# Schematic.net
KiCad netlist of a schematic drawn in EAGLE
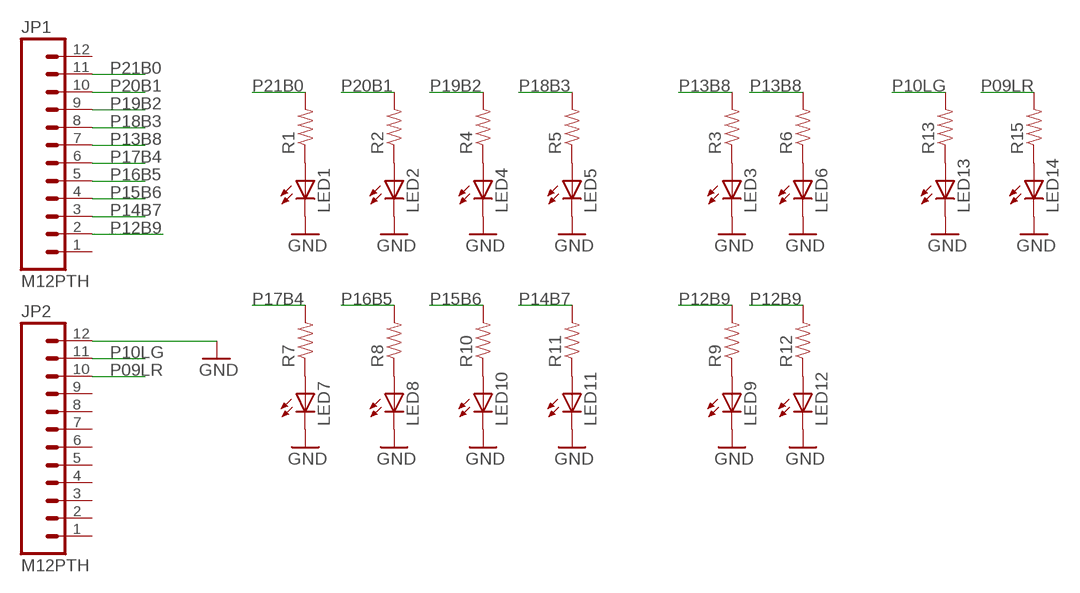
[diagram p0: schematic, sheet 1]

(export (version "E")
  (design (tool "Eeschema 10.0.6"))
  (components
    (comp (ref "JP1")
      (value "M12PTH")
      (footprint "eagle-import:1X12")
      (libsource (lib "eagle-import") (part "M12PTH"))
    )
    (comp (ref "JP2")
      (value "M12PTH")
      (footprint "eagle-import:1X12")
      (libsource (lib "eagle-import") (part "M12PTH"))
    )
    (comp (ref "LED1")
      (value "LEDCHIPLED_0805")
      (footprint "eagle-import:CHIPLED_0805")
      (libsource (lib "eagle-import") (part "LEDCHIPLED_0805"))
    )
    (comp (ref "LED2")
      (value "LEDCHIPLED_0805")
      (footprint "eagle-import:CHIPLED_0805")
      (libsource (lib "eagle-import") (part "LEDCHIPLED_0805"))
    )
    (comp (ref "LED3")
      (value "LEDCHIPLED_0805")
      (footprint "eagle-import:CHIPLED_0805")
      (libsource (lib "eagle-import") (part "LEDCHIPLED_0805"))
    )
    (comp (ref "LED4")
      (value "LEDCHIPLED_0805")
      (footprint "eagle-import:CHIPLED_0805")
      (libsource (lib "eagle-import") (part "LEDCHIPLED_0805"))
    )
    (comp (ref "LED5")
      (value "LEDCHIPLED_0805")
      (footprint "eagle-import:CHIPLED_0805")
      (libsource (lib "eagle-import") (part "LEDCHIPLED_0805"))
    )
    (comp (ref "LED6")
      (value "LEDCHIPLED_0805")
      (footprint "eagle-import:CHIPLED_0805")
      (libsource (lib "eagle-import") (part "LEDCHIPLED_0805"))
    )
    (comp (ref "LED7")
      (value "LEDCHIPLED_0805")
      (footprint "eagle-import:CHIPLED_0805")
      (libsource (lib "eagle-import") (part "LEDCHIPLED_0805"))
    )
    (comp (ref "LED8")
      (value "LEDCHIPLED_0805")
      (footprint "eagle-import:CHIPLED_0805")
      (libsource (lib "eagle-import") (part "LEDCHIPLED_0805"))
    )
    (comp (ref "LED9")
      (value "LEDCHIPLED_0805")
      (footprint "eagle-import:CHIPLED_0805")
      (libsource (lib "eagle-import") (part "LEDCHIPLED_0805"))
    )
    (comp (ref "LED10")
      (value "LEDCHIPLED_0805")
      (footprint "eagle-import:CHIPLED_0805")
      (libsource (lib "eagle-import") (part "LEDCHIPLED_0805"))
    )
    (comp (ref "LED11")
      (value "LEDCHIPLED_0805")
      (footprint "eagle-import:CHIPLED_0805")
      (libsource (lib "eagle-import") (part "LEDCHIPLED_0805"))
    )
    (comp (ref "LED12")
      (value "LEDCHIPLED_0805")
      (footprint "eagle-import:CHIPLED_0805")
      (libsource (lib "eagle-import") (part "LEDCHIPLED_0805"))
    )
    (comp (ref "LED13")
      (value "LEDCHIPLED_0805")
      (footprint "eagle-import:CHIPLED_0805")
      (libsource (lib "eagle-import") (part "LEDCHIPLED_0805"))
    )
    (comp (ref "LED14")
      (value "LEDCHIPLED_0805")
      (footprint "eagle-import:CHIPLED_0805")
      (libsource (lib "eagle-import") (part "LEDCHIPLED_0805"))
    )
    (comp (ref "R1")
      (value "RESISTOR0603-RES")
      (footprint "eagle-import:0603-RES")
      (libsource (lib "eagle-import") (part "RESISTOR0603-RES"))
    )
    (comp (ref "R2")
      (value "RESISTOR0603-RES")
      (footprint "eagle-import:0603-RES")
      (libsource (lib "eagle-import") (part "RESISTOR0603-RES"))
    )
    (comp (ref "R3")
      (value "RESISTOR0603-RES")
      (footprint "eagle-import:0603-RES")
      (libsource (lib "eagle-import") (part "RESISTOR0603-RES"))
    )
    (comp (ref "R4")
      (value "RESISTOR0603-RES")
      (footprint "eagle-import:0603-RES")
      (libsource (lib "eagle-import") (part "RESISTOR0603-RES"))
    )
    (comp (ref "R5")
      (value "RESISTOR0603-RES")
      (footprint "eagle-import:0603-RES")
      (libsource (lib "eagle-import") (part "RESISTOR0603-RES"))
    )
    (comp (ref "R6")
      (value "RESISTOR0603-RES")
      (footprint "eagle-import:0603-RES")
      (libsource (lib "eagle-import") (part "RESISTOR0603-RES"))
    )
    (comp (ref "R7")
      (value "RESISTOR0603-RES")
      (footprint "eagle-import:0603-RES")
      (libsource (lib "eagle-import") (part "RESISTOR0603-RES"))
    )
    (comp (ref "R8")
      (value "RESISTOR0603-RES")
      (footprint "eagle-import:0603-RES")
      (libsource (lib "eagle-import") (part "RESISTOR0603-RES"))
    )
    (comp (ref "R9")
      (value "RESISTOR0603-RES")
      (footprint "eagle-import:0603-RES")
      (libsource (lib "eagle-import") (part "RESISTOR0603-RES"))
    )
    (comp (ref "R10")
      (value "RESISTOR0603-RES")
      (footprint "eagle-import:0603-RES")
      (libsource (lib "eagle-import") (part "RESISTOR0603-RES"))
    )
    (comp (ref "R11")
      (value "RESISTOR0603-RES")
      (footprint "eagle-import:0603-RES")
      (libsource (lib "eagle-import") (part "RESISTOR0603-RES"))
    )
    (comp (ref "R12")
      (value "RESISTOR0603-RES")
      (footprint "eagle-import:0603-RES")
      (libsource (lib "eagle-import") (part "RESISTOR0603-RES"))
    )
    (comp (ref "R13")
      (value "RESISTOR0603-RES")
      (footprint "eagle-import:0603-RES")
      (libsource (lib "eagle-import") (part "RESISTOR0603-RES"))
    )
    (comp (ref "R15")
      (value "RESISTOR0603-RES")
      (footprint "eagle-import:0603-RES")
      (libsource (lib "eagle-import") (part "RESISTOR0603-RES"))
    )
  )
  (nets
    (net (code "1") (name "/P09LR") (class "Default")
      (node (ref "JP2") (pin "10") (pinfunction "10_10") (pintype "passive"))
      (node (ref "R15") (pin "2") (pinfunction "2_2") (pintype "passive"))
    )
    (net (code "2") (name "/P10LG") (class "Default")
      (node (ref "JP2") (pin "11") (pinfunction "11_11") (pintype "passive"))
      (node (ref "R13") (pin "2") (pinfunction "2_2") (pintype "passive"))
    )
    (net (code "3") (name "/P12B9") (class "Default")
      (node (ref "JP1") (pin "2") (pinfunction "2_2") (pintype "passive"))
      (node (ref "R12") (pin "2") (pinfunction "2_2") (pintype "passive"))
      (node (ref "R9") (pin "2") (pinfunction "2_2") (pintype "passive"))
    )
    (net (code "4") (name "/P13B8") (class "Default")
      (node (ref "JP1") (pin "7") (pinfunction "7_7") (pintype "passive"))
      (node (ref "R3") (pin "2") (pinfunction "2_2") (pintype "passive"))
      (node (ref "R6") (pin "2") (pinfunction "2_2") (pintype "passive"))
    )
    (net (code "5") (name "/P14B7") (class "Default")
      (node (ref "JP1") (pin "3") (pinfunction "3_3") (pintype "passive"))
      (node (ref "R11") (pin "2") (pinfunction "2_2") (pintype "passive"))
    )
    (net (code "6") (name "/P15B6") (class "Default")
      (node (ref "JP1") (pin "4") (pinfunction "4_4") (pintype "passive"))
      (node (ref "R10") (pin "2") (pinfunction "2_2") (pintype "passive"))
    )
    (net (code "7") (name "/P16B5") (class "Default")
      (node (ref "JP1") (pin "5") (pinfunction "5_5") (pintype "passive"))
      (node (ref "R8") (pin "2") (pinfunction "2_2") (pintype "passive"))
    )
    (net (code "8") (name "/P17B4") (class "Default")
      (node (ref "JP1") (pin "6") (pinfunction "6_6") (pintype "passive"))
      (node (ref "R7") (pin "2") (pinfunction "2_2") (pintype "passive"))
    )
    (net (code "9") (name "/P18B3") (class "Default")
      (node (ref "JP1") (pin "8") (pinfunction "8_8") (pintype "passive"))
      (node (ref "R5") (pin "2") (pinfunction "2_2") (pintype "passive"))
    )
    (net (code "10") (name "/P19B2") (class "Default")
      (node (ref "JP1") (pin "9") (pinfunction "9_9") (pintype "passive"))
      (node (ref "R4") (pin "2") (pinfunction "2_2") (pintype "passive"))
    )
    (net (code "11") (name "/P20B1") (class "Default")
      (node (ref "JP1") (pin "10") (pinfunction "10_10") (pintype "passive"))
      (node (ref "R2") (pin "2") (pinfunction "2_2") (pintype "passive"))
    )
    (net (code "12") (name "/P21B0") (class "Default")
      (node (ref "JP1") (pin "11") (pinfunction "11_11") (pintype "passive"))
      (node (ref "R1") (pin "2") (pinfunction "2_2") (pintype "passive"))
    )
    (net (code "13") (name "GND") (class "Default")
      (node (ref "JP2") (pin "12") (pinfunction "12_12") (pintype "passive"))
      (node (ref "LED1") (pin "C") (pinfunction "C_C") (pintype "passive"))
      (node (ref "LED10") (pin "C") (pinfunction "C_C") (pintype "passive"))
      (node (ref "LED11") (pin "C") (pinfunction "C_C") (pintype "passive"))
      (node (ref "LED12") (pin "C") (pinfunction "C_C") (pintype "passive"))
      (node (ref "LED13") (pin "C") (pinfunction "C_C") (pintype "passive"))
      (node (ref "LED14") (pin "C") (pinfunction "C_C") (pintype "passive"))
      (node (ref "LED2") (pin "C") (pinfunction "C_C") (pintype "passive"))
      (node (ref "LED3") (pin "C") (pinfunction "C_C") (pintype "passive"))
      (node (ref "LED4") (pin "C") (pinfunction "C_C") (pintype "passive"))
      (node (ref "LED5") (pin "C") (pinfunction "C_C") (pintype "passive"))
      (node (ref "LED6") (pin "C") (pinfunction "C_C") (pintype "passive"))
      (node (ref "LED7") (pin "C") (pinfunction "C_C") (pintype "passive"))
      (node (ref "LED8") (pin "C") (pinfunction "C_C") (pintype "passive"))
      (node (ref "LED9") (pin "C") (pinfunction "C_C") (pintype "passive"))
    )
    (net (code "14") (name "Net-(LED1-PadA)") (class "Default")
      (node (ref "LED1") (pin "A") (pinfunction "A_A") (pintype "passive"))
      (node (ref "R1") (pin "1") (pinfunction "1_1") (pintype "passive"))
    )
    (net (code "15") (name "Net-(LED2-PadA)") (class "Default")
      (node (ref "LED2") (pin "A") (pinfunction "A_A") (pintype "passive"))
      (node (ref "R2") (pin "1") (pinfunction "1_1") (pintype "passive"))
    )
    (net (code "16") (name "Net-(LED3-PadA)") (class "Default")
      (node (ref "LED3") (pin "A") (pinfunction "A_A") (pintype "passive"))
      (node (ref "R3") (pin "1") (pinfunction "1_1") (pintype "passive"))
    )
    (net (code "17") (name "Net-(LED4-PadA)") (class "Default")
      (node (ref "LED4") (pin "A") (pinfunction "A_A") (pintype "passive"))
      (node (ref "R4") (pin "1") (pinfunction "1_1") (pintype "passive"))
    )
    (net (code "18") (name "Net-(LED5-PadA)") (class "Default")
      (node (ref "LED5") (pin "A") (pinfunction "A_A") (pintype "passive"))
      (node (ref "R5") (pin "1") (pinfunction "1_1") (pintype "passive"))
    )
    (net (code "19") (name "Net-(LED6-PadA)") (class "Default")
      (node (ref "LED6") (pin "A") (pinfunction "A_A") (pintype "passive"))
      (node (ref "R6") (pin "1") (pinfunction "1_1") (pintype "passive"))
    )
    (net (code "20") (name "Net-(LED7-PadA)") (class "Default")
      (node (ref "LED7") (pin "A") (pinfunction "A_A") (pintype "passive"))
      (node (ref "R7") (pin "1") (pinfunction "1_1") (pintype "passive"))
    )
    (net (code "21") (name "Net-(LED8-PadA)") (class "Default")
      (node (ref "LED8") (pin "A") (pinfunction "A_A") (pintype "passive"))
      (node (ref "R8") (pin "1") (pinfunction "1_1") (pintype "passive"))
    )
    (net (code "22") (name "Net-(LED9-PadA)") (class "Default")
      (node (ref "LED9") (pin "A") (pinfunction "A_A") (pintype "passive"))
      (node (ref "R9") (pin "1") (pinfunction "1_1") (pintype "passive"))
    )
    (net (code "23") (name "Net-(LED10-PadA)") (class "Default")
      (node (ref "LED10") (pin "A") (pinfunction "A_A") (pintype "passive"))
      (node (ref "R10") (pin "1") (pinfunction "1_1") (pintype "passive"))
    )
    (net (code "24") (name "Net-(LED11-PadA)") (class "Default")
      (node (ref "LED11") (pin "A") (pinfunction "A_A") (pintype "passive"))
      (node (ref "R11") (pin "1") (pinfunction "1_1") (pintype "passive"))
    )
    (net (code "25") (name "Net-(LED12-PadA)") (class "Default")
      (node (ref "LED12") (pin "A") (pinfunction "A_A") (pintype "passive"))
      (node (ref "R12") (pin "1") (pinfunction "1_1") (pintype "passive"))
    )
    (net (code "26") (name "Net-(LED13-PadA)") (class "Default")
      (node (ref "LED13") (pin "A") (pinfunction "A_A") (pintype "passive"))
      (node (ref "R13") (pin "1") (pinfunction "1_1") (pintype "passive"))
    )
    (net (code "27") (name "Net-(LED14-PadA)") (class "Default")
      (node (ref "LED14") (pin "A") (pinfunction "A_A") (pintype "passive"))
      (node (ref "R15") (pin "1") (pinfunction "1_1") (pintype "passive"))
    )
    (net (code "28") (name "unconnected-(JP1-Pad1)") (class "Default")
      (node (ref "JP1") (pin "1") (pinfunction "1_1") (pintype "passive"))
    )
    (net (code "29") (name "unconnected-(JP1-Pad12)") (class "Default")
      (node (ref "JP1") (pin "12") (pinfunction "12_12") (pintype "passive"))
    )
    (net (code "30") (name "unconnected-(JP2-Pad1)") (class "Default")
      (node (ref "JP2") (pin "1") (pinfunction "1_1") (pintype "passive"))
    )
    (net (code "31") (name "unconnected-(JP2-Pad2)") (class "Default")
      (node (ref "JP2") (pin "2") (pinfunction "2_2") (pintype "passive"))
    )
    (net (code "32") (name "unconnected-(JP2-Pad3)") (class "Default")
      (node (ref "JP2") (pin "3") (pinfunction "3_3") (pintype "passive"))
    )
    (net (code "33") (name "unconnected-(JP2-Pad4)") (class "Default")
      (node (ref "JP2") (pin "4") (pinfunction "4_4") (pintype "passive"))
    )
    (net (code "34") (name "unconnected-(JP2-Pad5)") (class "Default")
      (node (ref "JP2") (pin "5") (pinfunction "5_5") (pintype "passive"))
    )
    (net (code "35") (name "unconnected-(JP2-Pad6)") (class "Default")
      (node (ref "JP2") (pin "6") (pinfunction "6_6") (pintype "passive"))
    )
    (net (code "36") (name "unconnected-(JP2-Pad7)") (class "Default")
      (node (ref "JP2") (pin "7") (pinfunction "7_7") (pintype "passive"))
    )
    (net (code "37") (name "unconnected-(JP2-Pad8)") (class "Default")
      (node (ref "JP2") (pin "8") (pinfunction "8_8") (pintype "passive"))
    )
    (net (code "38") (name "unconnected-(JP2-Pad9)") (class "Default")
      (node (ref "JP2") (pin "9") (pinfunction "9_9") (pintype "passive"))
    )
  )
)
